# FishTalk_Schematic_1.net
KiCad netlist of a schematic drawn in Altium Designer
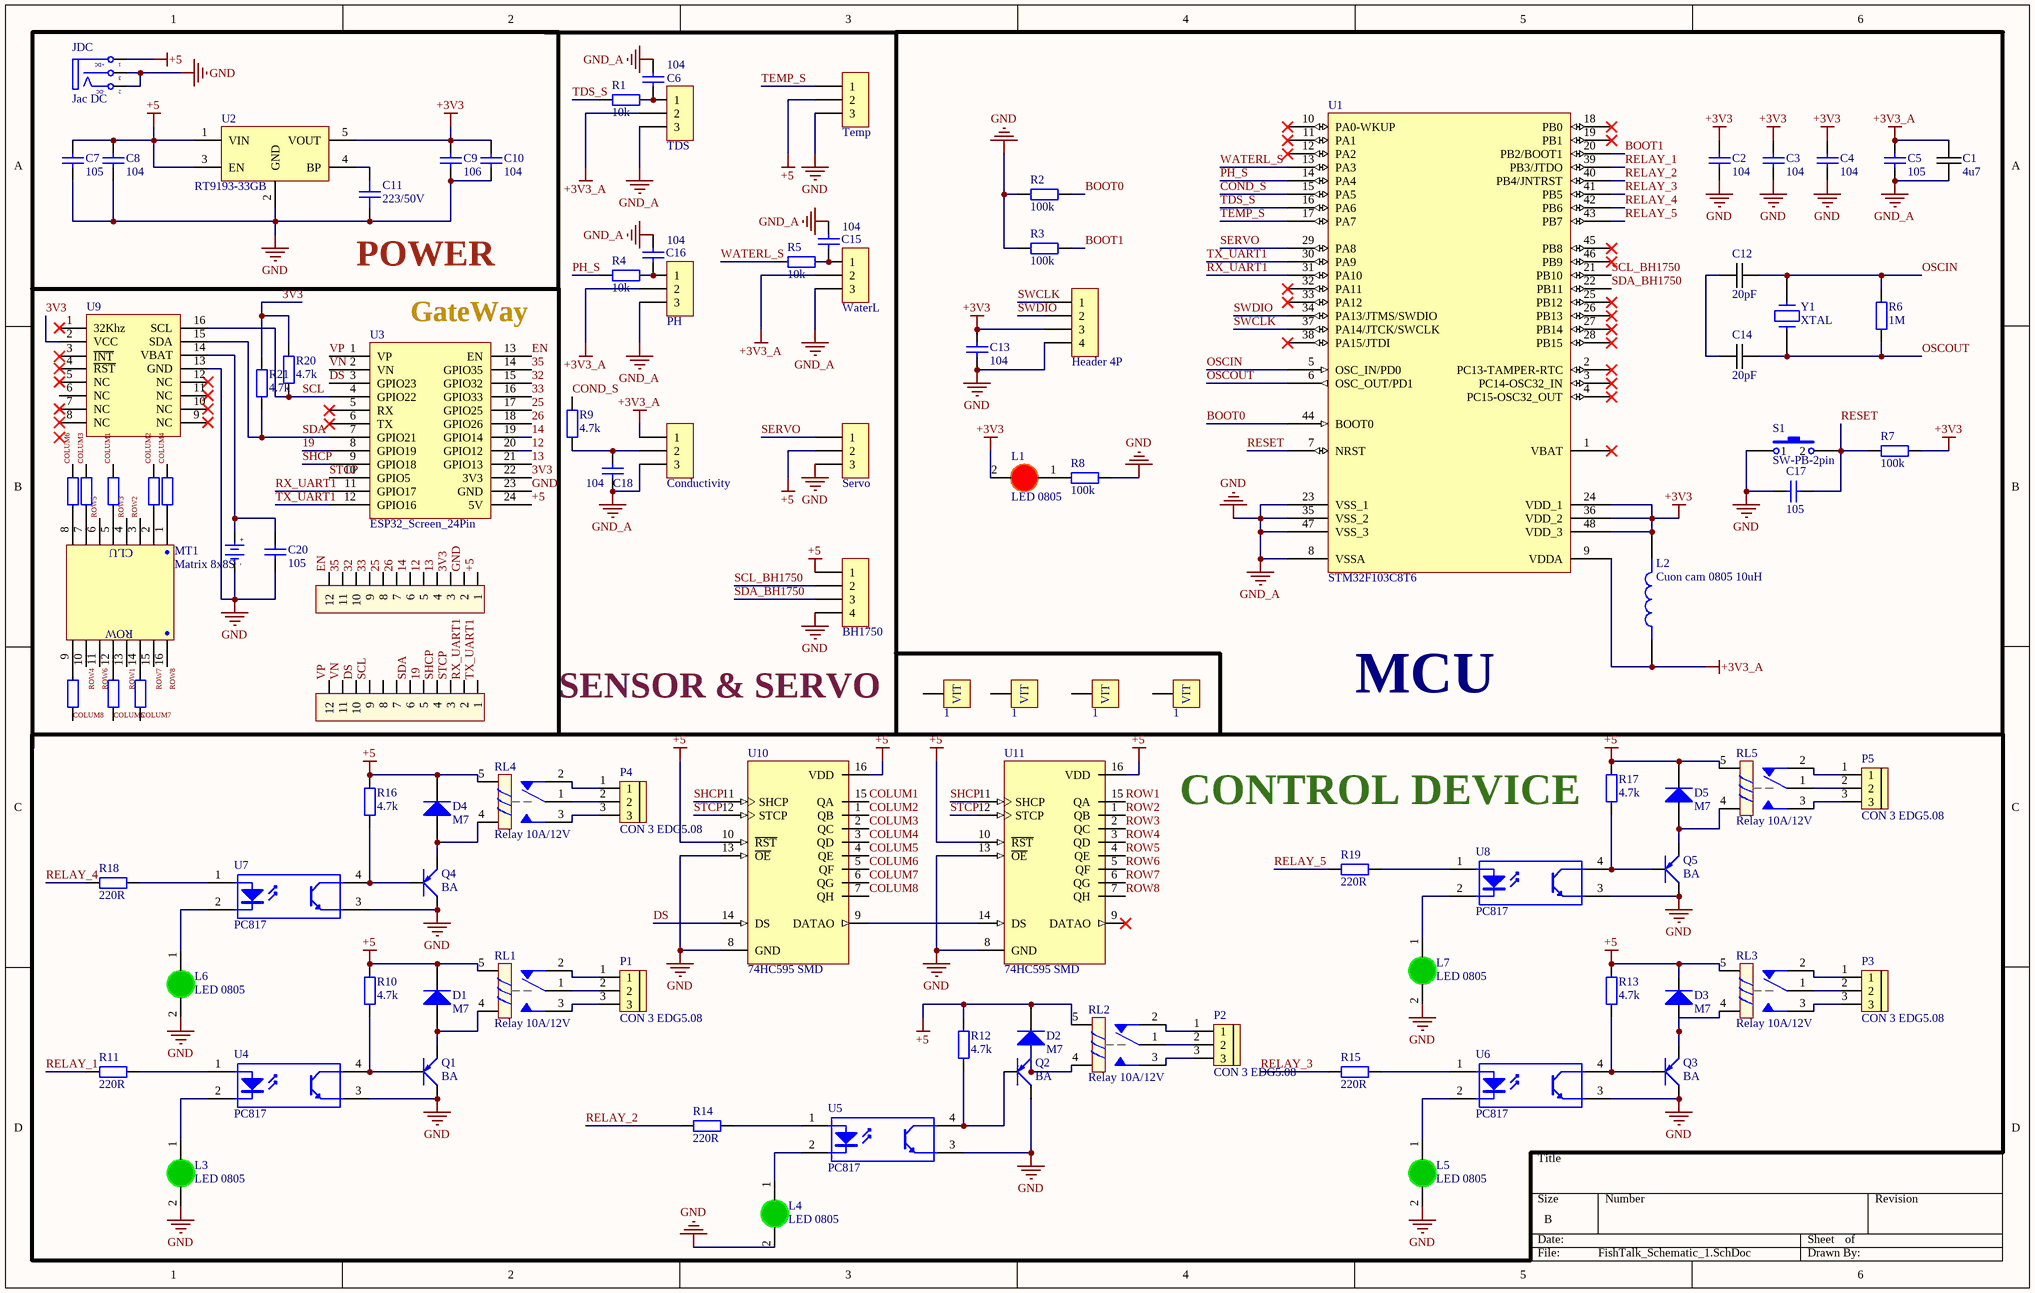
[diagram p0: FishTalk_Schematic_1.SchDoc]

(export (version "E")
  (design (tool "Eeschema 10.0.6"))
  (components
    (comp (ref "BH17")
      (value "BH1750")
      (footprint "XH2.54M-4")
      (description "Cắm")
      (libsource (lib "Header") (part "Header 4P 2.54 Duc Thang"))
    )
    (comp (ref "BT1")
      (value "CR1220 SMD")
      (footprint "DE PIN CR1220")
      (libsource (lib "Component") (part "De pin CR1220 SMD"))
    )
    (comp (ref "C1")
      (value "4u7")
      (footprint "0603C-GENERIC")
      (description "CAPACITOR 0603 CERAMIC")
      (fields
        (field (name "MANUFACTURER PART NUMBER") "C1608X5R1A475K")
        (field (name "MANUFACTURER") "TDK Corporation")
      )
      (libsource (lib "vh_altium_library") (part "0603C-4U7-10V-X5R-TDK"))
    )
    (comp (ref "C2")
      (value "104")
      (footprint "tu 0603")
      (description "Dán")
      (libsource (lib "Tu dien") (part "Tu 0603 104 50V 10%"))
    )
    (comp (ref "C3")
      (value "104")
      (footprint "tu 0603")
      (description "Dán")
      (libsource (lib "Tu dien") (part "Tu 0603 104 50V 10%"))
    )
    (comp (ref "C4")
      (value "104")
      (footprint "tu 0603")
      (description "Dán")
      (libsource (lib "Tu dien") (part "Tu 0603 104 50V 10%"))
    )
    (comp (ref "C5")
      (value "105")
      (footprint "tu 0603")
      (description "Dán")
      (libsource (lib "Tu dien") (part "Tu 0603 105 16V 20%"))
    )
    (comp (ref "C6")
      (value "104")
      (footprint "tu 0603")
      (description "Dán")
      (libsource (lib "Tu dien") (part "Tu 0603 104 50V 10%"))
    )
    (comp (ref "C7")
      (value "105")
      (footprint "tu 0603")
      (description "Dán")
      (libsource (lib "Tu dien") (part "Tu 0603 105 16V 20%"))
    )
    (comp (ref "C8")
      (value "104")
      (footprint "tu 0603")
      (description "Dán")
      (libsource (lib "Tu dien") (part "Tu 0603 104 50V 10%"))
    )
    (comp (ref "C9")
      (value "106")
      (footprint "tu 0603")
      (description "Dán")
      (libsource (lib "Tu dien") (part "Tu 0603 106 16V 20%"))
    )
    (comp (ref "C10")
      (value "104")
      (footprint "tu 0603")
      (description "Dán")
      (libsource (lib "Tu dien") (part "Tu 0603 104 50V 10%"))
    )
    (comp (ref "C11")
      (value "223/50V")
      (footprint "CAPC-0603 (1608)")
      (description "CAP CER 0.022uF 5% 50V X7R 0603")
      (fields (field (name "MPN") "CC0603JRX7R9BB223"))
      (libsource (lib "BYTECH_HW_LIB_2019 (1)") (part "CC0603JRX7R9BB223"))
    )
    (comp (ref "C12")
      (value "20pF")
      (footprint "0603C-GENERIC")
      (description "CAPACITOR 0603 CERAMIC")
      (fields
        (field (name "TOLERANCE") "±5%")
        (field (name "MANUFACTURER") "Murata Electronics North America")
      )
      (libsource (lib "vh_altium_library") (part "0603C-220PF-50V-C0G-MUR"))
    )
    (comp (ref "C13")
      (value "104")
      (footprint "tu 0603")
      (description "Dán")
      (libsource (lib "Tu dien") (part "Tu 0603 104 50V 10%"))
    )
    (comp (ref "C14")
      (value "20pF")
      (footprint "0603C-GENERIC")
      (description "CAPACITOR 0603 CERAMIC")
      (fields
        (field (name "TOLERANCE") "±5%")
        (field (name "MANUFACTURER") "Murata Electronics North America")
      )
      (libsource (lib "vh_altium_library") (part "0603C-220PF-50V-C0G-MUR"))
    )
    (comp (ref "C15")
      (value "104")
      (footprint "tu 0603")
      (description "Dán")
      (libsource (lib "Tu dien") (part "Tu 0603 104 50V 10%"))
    )
    (comp (ref "C16")
      (value "104")
      (footprint "tu 0603")
      (description "Dán")
      (libsource (lib "Tu dien") (part "Tu 0603 104 50V 10%"))
    )
    (comp (ref "C17")
      (value "105")
      (footprint "tu 0805")
      (description "Dán")
      (libsource (lib "Tu dien") (part "Tu 0805 105 50V 10%"))
    )
    (comp (ref "C18")
      (value "104")
      (footprint "tu 0603")
      (description "Dán")
      (libsource (lib "Tu dien") (part "Tu 0603 104 50V 10%"))
    )
    (comp (ref "C20")
      (value "105")
      (footprint "tu 0603")
      (description "Dán")
      (libsource (lib "Tu dien") (part "Tu 0603 105 16V 20%"))
    )
    (comp (ref "COND")
      (value "Conductivity")
      (footprint "XH2.54M-3")
      (description "Cắm")
      (libsource (lib "Header") (part "Header 3P 2.54 Duc Thang"))
    )
    (comp (ref "D1")
      (value "M7")
      (footprint "DIODE SMA")
      (description "Dán")
      (libsource (lib "Diode") (part "Diode M7 ( 4007 )"))
    )
    (comp (ref "D2")
      (value "M7")
      (footprint "DIODE SMA")
      (description "Dán")
      (libsource (lib "Diode") (part "Diode M7 ( 4007 )"))
    )
    (comp (ref "D3")
      (value "M7")
      (footprint "DIODE SMA")
      (description "Dán")
      (libsource (lib "Diode") (part "Diode M7 ( 4007 )"))
    )
    (comp (ref "D4")
      (value "M7")
      (footprint "DIODE SMA")
      (description "Dán")
      (libsource (lib "Diode") (part "Diode M7 ( 4007 )"))
    )
    (comp (ref "D5")
      (value "M7")
      (footprint "DIODE SMA")
      (description "Dán")
      (libsource (lib "Diode") (part "Diode M7 ( 4007 )"))
    )
    (comp (ref "H3")
      (value "Header 4P")
      (footprint "XH2.54M-4")
      (description "Cắm")
      (libsource (lib "Header") (part "Header 4P 2.54 Duc Thang"))
    )
    (comp (ref "H8")
      (value "Header 12P")
      (footprint "XH2.54M-12")
      (description "Cắm")
      (libsource (lib "Header") (part "Header 12P"))
    )
    (comp (ref "H9")
      (value "Header 12P")
      (footprint "XH2.54M-12")
      (description "Cắm")
      (libsource (lib "Header") (part "Header 12P"))
    )
    (comp (ref "JDC")
      (value "Jac DC")
      (footprint "DC-IN")
      (description "Jac DC input")
      (libsource (lib "syhaunguyen") (part "DCIN"))
    )
    (comp (ref "L1")
      (value "LED 0805")
      (footprint "LED-1206-Red")
      (description "Dán")
      (libsource (lib "Led") (part "LED 1206 Do"))
    )
    (comp (ref "L2")
      (value "Cuon cam 0805 10uH")
      (footprint "Inductor 0805")
      (description "1.5ÂµH Unshielded Multilayer Inductor 700mA 220mOhm 0805 (2012 Metric)")
      (fields (field (name "MF") "Laird") (field (name "MP") "CPI0805G1R5R-10"))
      (libsource (lib "Cuon Cam") (part "Cuon cam 0805"))
    )
    (comp (ref "L3")
      (value "LED 0805")
      (footprint "LED-1206-Green")
      (description "Dán")
      (libsource (lib "Led") (part "LED 1206 Xanh La"))
    )
    (comp (ref "L4")
      (value "LED 0805")
      (footprint "LED-1206-Green")
      (description "Dán")
      (libsource (lib "Led") (part "LED 1206 Xanh La"))
    )
    (comp (ref "L5")
      (value "LED 0805")
      (footprint "LED-1206-Green")
      (description "Dán")
      (libsource (lib "Led") (part "LED 1206 Xanh La"))
    )
    (comp (ref "L6")
      (value "LED 0805")
      (footprint "LED-1206-Green")
      (description "Dán")
      (libsource (lib "Led") (part "LED 1206 Xanh La"))
    )
    (comp (ref "L7")
      (value "LED 0805")
      (footprint "LED-1206-Green")
      (description "Dán")
      (libsource (lib "Led") (part "LED 1206 Xanh La"))
    )
    (comp (ref "MT1")
      (value "Matrix 8x8S")
      (footprint "Matrix")
      (description "Matrix 8x8,  Single colour")
      (libsource (lib "Library") (part "LED 8x8S"))
    )
    (comp (ref "P1")
      (value "CON 3 EDG5.08")
      (footprint "Con 3 KF301 5.08")
      (description "Cắm")
      (libsource (lib "Connector") (part "CON 3 EDG5.08"))
    )
    (comp (ref "P2")
      (value "CON 3 EDG5.08")
      (footprint "Con 3 KF301 5.08")
      (description "Cắm")
      (libsource (lib "Connector") (part "CON 3 EDG5.08"))
    )
    (comp (ref "P3")
      (value "CON 3 EDG5.08")
      (footprint "Con 3 KF301 5.08")
      (description "Cắm")
      (libsource (lib "Connector") (part "CON 3 EDG5.08"))
    )
    (comp (ref "P4")
      (value "CON 3 EDG5.08")
      (footprint "Con 3 KF301 5.08")
      (description "Cắm")
      (libsource (lib "Connector") (part "CON 3 EDG5.08"))
    )
    (comp (ref "P5")
      (value "CON 3 EDG5.08")
      (footprint "Con 3 KF301 5.08")
      (description "Cắm")
      (libsource (lib "Connector") (part "CON 3 EDG5.08"))
    )
    (comp (ref "PH")
      (value "PH")
      (footprint "XH2.54M-3")
      (description "Cắm")
      (libsource (lib "Header") (part "Header 3P 2.54 Duc Thang"))
    )
    (comp (ref "Q1")
      (value "BA")
      (footprint "SOT23")
      (description "PNP 600mW, ECB")
      (libsource (lib "TranFet") (part "A1015 BA SMD"))
    )
    (comp (ref "Q2")
      (value "BA")
      (footprint "SOT23")
      (description "PNP 600mW, ECB")
      (libsource (lib "TranFet") (part "A1015 BA SMD"))
    )
    (comp (ref "Q3")
      (value "BA")
      (footprint "SOT23")
      (description "PNP 600mW, ECB")
      (libsource (lib "TranFet") (part "A1015 BA SMD"))
    )
    (comp (ref "Q4")
      (value "BA")
      (footprint "SOT23")
      (description "PNP 600mW, ECB")
      (libsource (lib "TranFet") (part "A1015 BA SMD"))
    )
    (comp (ref "Q5")
      (value "BA")
      (footprint "SOT23")
      (description "PNP 600mW, ECB")
      (libsource (lib "TranFet") (part "A1015 BA SMD"))
    )
    (comp (ref "R1")
      (value "10k")
      (footprint "tro smd 0603")
      (description "Dán")
      (libsource (lib "Dien Tro") (part "Tro 0603 1% 10k"))
    )
    (comp (ref "R2")
      (value "100k")
      (footprint "tro smd 0603")
      (description "Dán")
      (libsource (lib "Dien Tro") (part "Tro 0603 5% 100k"))
    )
    (comp (ref "R3")
      (value "100k")
      (footprint "tro smd 0603")
      (description "Dán")
      (libsource (lib "Dien Tro") (part "Tro 0603 5% 100k"))
    )
    (comp (ref "R4")
      (value "10k")
      (footprint "tro smd 0603")
      (description "Dán")
      (libsource (lib "Dien Tro") (part "Tro 0603 1% 10k"))
    )
    (comp (ref "R5")
      (value "10k")
      (footprint "tro smd 0603")
      (description "Dán")
      (libsource (lib "Dien Tro") (part "Tro 0603 1% 10k"))
    )
    (comp (ref "R6")
      (value "1M")
      (footprint "tro smd 0603")
      (description "Dán")
      (libsource (lib "Dien Tro") (part "Tro 0603 5% 1M"))
    )
    (comp (ref "R7")
      (value "100k")
      (footprint "tro smd 0603")
      (description "Dán")
      (libsource (lib "Dien Tro") (part "Tro 0603 5% 100k"))
    )
    (comp (ref "R8")
      (value "100k")
      (footprint "tro smd 0603")
      (description "Dán")
      (libsource (lib "Dien Tro") (part "Tro 0603 5% 100k"))
    )
    (comp (ref "R9")
      (value "4.7k")
      (footprint "tro smd 0603")
      (description "Dán")
      (libsource (lib "Dien Tro") (part "Tro 0603 1% 10k"))
    )
    (comp (ref "R10")
      (value "4.7k")
      (footprint "tro smd 0603")
      (description "Dán")
      (libsource (lib "Dien Tro") (part "Tro 0603 1% 10k"))
    )
    (comp (ref "R11")
      (value "220R")
      (footprint "tro smd 0603")
      (description "Dán")
      (libsource (lib "Dien Tro") (part "Tro 0603 5% 220R"))
    )
    (comp (ref "R12")
      (value "4.7k")
      (footprint "tro smd 0603")
      (description "Dán")
      (libsource (lib "Dien Tro") (part "Tro 0603 1% 10k"))
    )
    (comp (ref "R13")
      (value "4.7k")
      (footprint "tro smd 0603")
      (description "Dán")
      (libsource (lib "Dien Tro") (part "Tro 0603 1% 10k"))
    )
    (comp (ref "R14")
      (value "220R")
      (footprint "tro smd 0603")
      (description "Dán")
      (libsource (lib "Dien Tro") (part "Tro 0603 5% 220R"))
    )
    (comp (ref "R15")
      (value "220R")
      (footprint "tro smd 0603")
      (description "Dán")
      (libsource (lib "Dien Tro") (part "Tro 0603 5% 220R"))
    )
    (comp (ref "R16")
      (value "4.7k")
      (footprint "tro smd 0603")
      (description "Dán")
      (libsource (lib "Dien Tro") (part "Tro 0603 1% 10k"))
    )
    (comp (ref "R17")
      (value "4.7k")
      (footprint "tro smd 0603")
      (description "Dán")
      (libsource (lib "Dien Tro") (part "Tro 0603 1% 10k"))
    )
    (comp (ref "R18")
      (value "220R")
      (footprint "tro smd 0603")
      (description "Dán")
      (libsource (lib "Dien Tro") (part "Tro 0603 5% 220R"))
    )
    (comp (ref "R19")
      (value "220R")
      (footprint "tro smd 0603")
      (description "Dán")
      (libsource (lib "Dien Tro") (part "Tro 0603 5% 220R"))
    )
    (comp (ref "R20")
      (value "4.7k")
      (footprint "tro smd 0603")
      (description "Dán")
      (libsource (lib "Dien Tro") (part "Tro 0603 1% 10k"))
    )
    (comp (ref "R21")
      (value "4.7k")
      (footprint "tro smd 0603")
      (description "Dán")
      (libsource (lib "Dien Tro") (part "Tro 0603 1% 10k"))
    )
    (comp (ref "R22")
      (value "560R")
      (footprint "tro smd 0603")
      (description "Dán")
      (libsource (lib "Dien Tro") (part "Tro 0603 5% 100k"))
    )
    (comp (ref "R23")
      (value "560R")
      (footprint "tro smd 0603")
      (description "Dán")
      (libsource (lib "Dien Tro") (part "Tro 0603 5% 100k"))
    )
    (comp (ref "R24")
      (value "560R")
      (footprint "tro smd 0603")
      (description "Dán")
      (libsource (lib "Dien Tro") (part "Tro 0603 5% 100k"))
    )
    (comp (ref "R25")
      (value "560R")
      (footprint "tro smd 0603")
      (description "Dán")
      (libsource (lib "Dien Tro") (part "Tro 0603 5% 100k"))
    )
    (comp (ref "R26")
      (value "560R")
      (footprint "tro smd 0603")
      (description "Dán")
      (libsource (lib "Dien Tro") (part "Tro 0603 5% 100k"))
    )
    (comp (ref "R27")
      (value "560R")
      (footprint "tro smd 0603")
      (description "Dán")
      (libsource (lib "Dien Tro") (part "Tro 0603 5% 100k"))
    )
    (comp (ref "R28")
      (value "560R")
      (footprint "tro smd 0603")
      (description "Dán")
      (libsource (lib "Dien Tro") (part "Tro 0603 5% 100k"))
    )
    (comp (ref "R29")
      (value "560R")
      (footprint "tro smd 0603")
      (description "Dán")
      (libsource (lib "Dien Tro") (part "Tro 0603 5% 100k"))
    )
    (comp (ref "RL1")
      (value "Relay 10A/12V")
      (footprint "RL_SPDT_10A")
      (description "Relay SPDT,10A - 12VDC 5 Pin")
      (libsource (lib "syhaunguyen") (part "Relay 1"))
    )
    (comp (ref "RL2")
      (value "Relay 10A/12V")
      (footprint "RL_SPDT_10A")
      (description "Relay SPDT,10A - 12VDC 5 Pin")
      (libsource (lib "syhaunguyen") (part "Relay 1"))
    )
    (comp (ref "RL3")
      (value "Relay 10A/12V")
      (footprint "RL_SPDT_10A")
      (description "Relay SPDT,10A - 12VDC 5 Pin")
      (libsource (lib "syhaunguyen") (part "Relay 1"))
    )
    (comp (ref "RL4")
      (value "Relay 10A/12V")
      (footprint "RL_SPDT_10A")
      (description "Relay SPDT,10A - 12VDC 5 Pin")
      (libsource (lib "syhaunguyen") (part "Relay 1"))
    )
    (comp (ref "RL5")
      (value "Relay 10A/12V")
      (footprint "RL_SPDT_10A")
      (description "Relay SPDT,10A - 12VDC 5 Pin")
      (libsource (lib "syhaunguyen") (part "Relay 1"))
    )
    (comp (ref "S1")
      (value "SW-PB-2pin")
      (footprint "thuvien_altium:SW_B3U-1000P")
      (description "Switch")
      (fields (field (name "PUBLISHER") "Altium Limited"))
      (libsource (lib "thuvien_altium") (part "SW-PB-2pin"))
    )
    (comp (ref "SERVO")
      (value "Servo")
      (footprint "XH2.54M-3")
      (description "Cắm")
      (libsource (lib "Header") (part "Header 3P 2.54 Duc Thang"))
    )
    (comp (ref "TDS")
      (value "TDS")
      (footprint "XH2.54M-3")
      (description "Cắm")
      (libsource (lib "Header") (part "Header 3P 2.54 Duc Thang"))
    )
    (comp (ref "TEMP")
      (value "Temp")
      (footprint "XH2.54M-3")
      (description "Cắm")
      (libsource (lib "Header") (part "Header 3P 2.54 Duc Thang"))
    )
    (comp (ref "U1")
      (value "STM32F103C8T6")
      (footprint "MinhTien_PcbLib:LQFP48_L")
      (description "STM32 ARM-based 32-bit MCU with 64 Kbytes Flash, 48-pin LQFP, Industrial Temperature")
      (fields (field (name "PUBLISHER") "Altium Limited"))
      (libsource (lib "MinhTien_SCHLib") (part "STM32F103C8T6"))
    )
    (comp (ref "U2")
      (value "RT9193-33GB")
      (footprint "MinhTien_PcbLib:SOT23-5AL")
      (description "1A Regulator")
      (libsource (lib "MinhTien_SCHLib") (part "RT9193"))
    )
    (comp (ref "U3")
      (value "ESP32_Screen_24Pin")
      (footprint "ESP32_Module_Screen_24Pin_N3D")
      (libsource (lib "Schlib1_fist_tank") (part "ESP32_Screen_24Pin"))
    )
    (comp (ref "U4")
      (value "PC817")
      (footprint "MinhTien_PCBLib:PhotoCoupler_SMD")
      (description "4-Pin Phototransistor Optocoupler")
      (fields (field (name "PUBLISHER") "Altium Limited"))
      (libsource (lib "MinhTien_SCHLib") (part "PC817"))
    )
    (comp (ref "U5")
      (value "PC817")
      (footprint "MinhTien_PCBLib:PhotoCoupler_SMD")
      (description "4-Pin Phototransistor Optocoupler")
      (fields (field (name "PUBLISHER") "Altium Limited"))
      (libsource (lib "MinhTien_SCHLib") (part "PC817"))
    )
    (comp (ref "U6")
      (value "PC817")
      (footprint "MinhTien_PCBLib:PhotoCoupler_SMD")
      (description "4-Pin Phototransistor Optocoupler")
      (fields (field (name "PUBLISHER") "Altium Limited"))
      (libsource (lib "MinhTien_SCHLib") (part "PC817"))
    )
    (comp (ref "U7")
      (value "PC817")
      (footprint "MinhTien_PCBLib:PhotoCoupler_SMD")
      (description "4-Pin Phototransistor Optocoupler")
      (fields (field (name "PUBLISHER") "Altium Limited"))
      (libsource (lib "MinhTien_SCHLib") (part "PC817"))
    )
    (comp (ref "U8")
      (value "PC817")
      (footprint "MinhTien_PCBLib:PhotoCoupler_SMD")
      (description "4-Pin Phototransistor Optocoupler")
      (fields (field (name "PUBLISHER") "Altium Limited"))
      (libsource (lib "MinhTien_SCHLib") (part "PC817"))
    )
    (comp (ref "U9")
      (value "DS3231 SMD")
      (footprint "SOIC 16")
      (description "SOIC")
      (libsource (lib "IC") (part "DS3231 SMD"))
    )
    (comp (ref "U10")
      (value "74HC595 SMD")
      (footprint "SOP 16")
      (description "Dán")
      (libsource (lib "IC") (part "74HC595 SMD"))
    )
    (comp (ref "U11")
      (value "74HC595 SMD")
      (footprint "SOP 16")
      (description "Dán")
      (libsource (lib "IC") (part "74HC595 SMD"))
    )
    (comp (ref "VIT1")
      (value "1")
      (footprint "Screw octagon 3.81mm")
      (description "Vit xuyen lo")
      (libsource (lib "Connector") (part "VIT"))
    )
    (comp (ref "VIT2")
      (value "1")
      (footprint "Screw octagon 3.81mm")
      (description "Vit xuyen lo")
      (libsource (lib "Connector") (part "VIT"))
    )
    (comp (ref "VIT3")
      (value "1")
      (footprint "Screw octagon 3.81mm")
      (description "Vit xuyen lo")
      (libsource (lib "Connector") (part "VIT"))
    )
    (comp (ref "VIT4")
      (value "1")
      (footprint "Screw octagon 3.81mm")
      (description "Vit xuyen lo")
      (libsource (lib "Connector") (part "VIT"))
    )
    (comp (ref "WATER")
      (value "WaterL")
      (footprint "XH2.54M-3")
      (description "Cắm")
      (libsource (lib "Header") (part "Header 3P 2.54 Duc Thang"))
    )
    (comp (ref "Y1")
      (value "XTAL")
      (footprint "XTAL")
      (description "Crystal")
      (libsource (lib "iDr.ALTIUM") (part "XTAL"))
    )
  )
  (nets
    (net (code "1") (name "+3V3") (class "Default")
      (node (ref "C10") (pin "1") (pinfunction "1_1") (pintype "passive"))
      (node (ref "C13") (pin "1") (pinfunction "1_1") (pintype "passive"))
      (node (ref "C2") (pin "1") (pinfunction "1_1") (pintype "passive"))
      (node (ref "C3") (pin "1") (pinfunction "1_1") (pintype "passive"))
      (node (ref "C4") (pin "1") (pinfunction "1_1") (pintype "passive"))
      (node (ref "C9") (pin "1") (pinfunction "1_1") (pintype "passive"))
      (node (ref "H3") (pin "3") (pinfunction "3_3") (pintype "passive"))
      (node (ref "L1") (pin "2") (pinfunction "K_2") (pintype "passive"))
      (node (ref "L2") (pin "2") (pinfunction "2_2") (pintype "passive"))
      (node (ref "R7") (pin "2") (pinfunction "2_2") (pintype "passive"))
      (node (ref "U1") (pin "24") (pinfunction "VDD_1_24") (pintype "power_in"))
      (node (ref "U1") (pin "36") (pinfunction "VDD_2_36") (pintype "power_in"))
      (node (ref "U1") (pin "48") (pinfunction "VDD_3_48") (pintype "power_in"))
      (node (ref "U2") (pin "5") (pinfunction "VOUT_5") (pintype "passive"))
    )
    (net (code "2") (name "+3V3_A") (class "Default")
      (node (ref "C1") (pin "1") (pintype "passive"))
      (node (ref "C5") (pin "1") (pinfunction "1_1") (pintype "passive"))
      (node (ref "COND") (pin "1") (pinfunction "1_1") (pintype "passive"))
      (node (ref "L2") (pin "1") (pinfunction "1_1") (pintype "passive"))
      (node (ref "PH") (pin "2") (pinfunction "2_2") (pintype "passive"))
      (node (ref "TDS") (pin "2") (pinfunction "2_2") (pintype "passive"))
      (node (ref "U1") (pin "9") (pinfunction "VDDA_9") (pintype "power_in"))
      (node (ref "WATER") (pin "2") (pinfunction "2_2") (pintype "passive"))
    )
    (net (code "3") (name "+5") (class "Default")
      (node (ref "BH17") (pin "1") (pinfunction "1_1") (pintype "passive"))
      (node (ref "C7") (pin "1") (pinfunction "1_1") (pintype "passive"))
      (node (ref "C8") (pin "1") (pinfunction "1_1") (pintype "passive"))
      (node (ref "D1") (pin "2") (pinfunction "K_2") (pintype "passive"))
      (node (ref "D2") (pin "2") (pinfunction "K_2") (pintype "passive"))
      (node (ref "D3") (pin "2") (pinfunction "K_2") (pintype "passive"))
      (node (ref "D4") (pin "2") (pinfunction "K_2") (pintype "passive"))
      (node (ref "D5") (pin "2") (pinfunction "K_2") (pintype "passive"))
      (node (ref "H9") (pin "1") (pinfunction "1_1") (pintype "passive"))
      (node (ref "JDC") (pin "1") (pinfunction "T_1") (pintype "passive"))
      (node (ref "R10") (pin "2") (pinfunction "2_2") (pintype "passive"))
      (node (ref "R12") (pin "2") (pinfunction "2_2") (pintype "passive"))
      (node (ref "R13") (pin "2") (pinfunction "2_2") (pintype "passive"))
      (node (ref "R16") (pin "2") (pinfunction "2_2") (pintype "passive"))
      (node (ref "R17") (pin "2") (pinfunction "2_2") (pintype "passive"))
      (node (ref "RL1") (pin "5") (pinfunction "5_5") (pintype "passive"))
      (node (ref "RL2") (pin "5") (pinfunction "5_5") (pintype "passive"))
      (node (ref "RL3") (pin "5") (pinfunction "5_5") (pintype "passive"))
      (node (ref "RL4") (pin "5") (pinfunction "5_5") (pintype "passive"))
      (node (ref "RL5") (pin "5") (pinfunction "5_5") (pintype "passive"))
      (node (ref "SERVO") (pin "2") (pinfunction "2_2") (pintype "passive"))
      (node (ref "TEMP") (pin "2") (pinfunction "2_2") (pintype "passive"))
      (node (ref "U10") (pin "10") (pinfunction "~{RST}_10") (pintype "input"))
      (node (ref "U10") (pin "16") (pinfunction "VDD_16") (pintype "power_in"))
      (node (ref "U11") (pin "10") (pinfunction "~{RST}_10") (pintype "input"))
      (node (ref "U11") (pin "16") (pinfunction "VDD_16") (pintype "power_in"))
      (node (ref "U2") (pin "1") (pinfunction "VIN_1") (pintype "passive"))
      (node (ref "U2") (pin "3") (pinfunction "EN_3") (pintype "passive"))
      (node (ref "U3") (pin "24") (pinfunction "5V_24") (pintype "passive"))
    )
    (net (code "4") (name "/3V3") (class "Default")
      (node (ref "H9") (pin "3") (pinfunction "3_3") (pintype "passive"))
      (node (ref "R20") (pin "2") (pinfunction "2_2") (pintype "passive"))
      (node (ref "R21") (pin "2") (pinfunction "2_2") (pintype "passive"))
      (node (ref "U3") (pin "22") (pinfunction "3V3_22") (pintype "passive"))
      (node (ref "U9") (pin "2") (pinfunction "VCC_2") (pintype "power_in"))
    )
    (net (code "5") (name "/12") (class "Default")
      (node (ref "H9") (pin "5") (pinfunction "5_5") (pintype "passive"))
      (node (ref "U3") (pin "20") (pinfunction "GPIO12_20") (pintype "passive"))
    )
    (net (code "6") (name "/13") (class "Default")
      (node (ref "H9") (pin "4") (pinfunction "4_4") (pintype "passive"))
      (node (ref "U3") (pin "21") (pinfunction "GPIO13_21") (pintype "passive"))
    )
    (net (code "7") (name "/14") (class "Default")
      (node (ref "H9") (pin "6") (pinfunction "6_6") (pintype "passive"))
      (node (ref "U3") (pin "19") (pinfunction "GPIO14_19") (pintype "passive"))
    )
    (net (code "8") (name "/19") (class "Default")
      (node (ref "H8") (pin "5") (pinfunction "5_5") (pintype "passive"))
      (node (ref "U3") (pin "8") (pinfunction "GPIO19_8") (pintype "passive"))
    )
    (net (code "9") (name "/25") (class "Default")
      (node (ref "H9") (pin "8") (pinfunction "8_8") (pintype "passive"))
      (node (ref "U3") (pin "17") (pinfunction "GPIO25_17") (pintype "passive"))
    )
    (net (code "10") (name "/26") (class "Default")
      (node (ref "H9") (pin "7") (pinfunction "7_7") (pintype "passive"))
      (node (ref "U3") (pin "18") (pinfunction "GPIO26_18") (pintype "passive"))
    )
    (net (code "11") (name "/32") (class "Default")
      (node (ref "H9") (pin "10") (pinfunction "10_10") (pintype "passive"))
      (node (ref "U3") (pin "15") (pinfunction "GPIO32_15") (pintype "passive"))
    )
    (net (code "12") (name "/33") (class "Default")
      (node (ref "H9") (pin "9") (pinfunction "9_9") (pintype "passive"))
      (node (ref "U3") (pin "16") (pinfunction "GPIO33_16") (pintype "passive"))
    )
    (net (code "13") (name "/35") (class "Default")
      (node (ref "H9") (pin "11") (pinfunction "11_11") (pintype "passive"))
      (node (ref "U3") (pin "14") (pinfunction "GPIO35_14") (pintype "passive"))
    )
    (net (code "14") (name "/BOOT0") (class "Default")
      (node (ref "R2") (pin "2") (pinfunction "2_2") (pintype "passive"))
      (node (ref "U1") (pin "44") (pinfunction "BOOT0_44") (pintype "input"))
    )
    (net (code "15") (name "/BOOT1") (class "Default")
      (node (ref "R3") (pin "2") (pinfunction "2_2") (pintype "passive"))
      (node (ref "U1") (pin "20") (pinfunction "PB2/BOOT1_20") (pintype "bidirectional"))
    )
    (net (code "16") (name "/COLUM1") (class "Default")
      (node (ref "R24") (pin "2") (pinfunction "2_2") (pintype "passive"))
      (node (ref "U10") (pin "15") (pinfunction "QA_15") (pintype "tri_state"))
    )
    (net (code "17") (name "/COLUM2") (class "Default")
      (node (ref "R25") (pin "2") (pinfunction "2_2") (pintype "passive"))
      (node (ref "U10") (pin "1") (pinfunction "QB_1") (pintype "tri_state"))
    )
    (net (code "18") (name "/COLUM3") (class "Default")
      (node (ref "R23") (pin "2") (pinfunction "2_2") (pintype "passive"))
      (node (ref "U10") (pin "2") (pinfunction "QC_2") (pintype "tri_state"))
    )
    (net (code "19") (name "/COLUM4") (class "Default")
      (node (ref "R26") (pin "2") (pinfunction "2_2") (pintype "passive"))
      (node (ref "U10") (pin "3") (pinfunction "QD_3") (pintype "tri_state"))
    )
    (net (code "20") (name "/COLUM5") (class "Default")
      (node (ref "R28") (pin "1") (pinfunction "1_1") (pintype "passive"))
      (node (ref "U10") (pin "4") (pinfunction "QE_4") (pintype "tri_state"))
    )
    (net (code "21") (name "/COLUM6") (class "Default")
      (node (ref "R22") (pin "2") (pinfunction "2_2") (pintype "passive"))
      (node (ref "U10") (pin "5") (pinfunction "QF_5") (pintype "tri_state"))
    )
    (net (code "22") (name "/COLUM7") (class "Default")
      (node (ref "R29") (pin "1") (pinfunction "1_1") (pintype "passive"))
      (node (ref "U10") (pin "6") (pinfunction "QG_6") (pintype "tri_state"))
    )
    (net (code "23") (name "/COLUM8") (class "Default")
      (node (ref "R27") (pin "1") (pinfunction "1_1") (pintype "passive"))
      (node (ref "U10") (pin "7") (pinfunction "QH_7") (pintype "tri_state"))
    )
    (net (code "24") (name "/COND_S") (class "Default")
      (node (ref "R9") (pin "1") (pinfunction "1_1") (pintype "passive"))
      (node (ref "U1") (pin "15") (pinfunction "PA5_15") (pintype "bidirectional"))
    )
    (net (code "25") (name "/DS") (class "Default")
      (node (ref "H8") (pin "10") (pinfunction "10_10") (pintype "passive"))
      (node (ref "U10") (pin "14") (pinfunction "DS_14") (pintype "input"))
      (node (ref "U3") (pin "3") (pinfunction "GPIO23_3") (pintype "passive"))
    )
    (net (code "26") (name "/EN") (class "Default")
      (node (ref "H9") (pin "12") (pinfunction "12_12") (pintype "passive"))
      (node (ref "U3") (pin "13") (pinfunction "EN_13") (pintype "passive"))
    )
    (net (code "27") (name "/OSCIN") (class "Default")
      (node (ref "C12") (pin "2") (pintype "passive"))
      (node (ref "R6") (pin "2") (pinfunction "2_2") (pintype "passive"))
      (node (ref "U1") (pin "5") (pinfunction "OSC_IN/PD0_5") (pintype "input"))
      (node (ref "Y1") (pin "2") (pinfunction "2_2") (pintype "passive"))
    )
    (net (code "28") (name "/OSCOUT") (class "Default")
      (node (ref "C14") (pin "2") (pintype "passive"))
      (node (ref "R6") (pin "1") (pinfunction "1_1") (pintype "passive"))
      (node (ref "U1") (pin "6") (pinfunction "OSC_OUT/PD1_6") (pintype "output"))
      (node (ref "Y1") (pin "1") (pinfunction "1_1") (pintype "passive"))
    )
    (net (code "29") (name "/PH_S") (class "Default")
      (node (ref "R4") (pin "1") (pinfunction "1_1") (pintype "passive"))
      (node (ref "U1") (pin "14") (pinfunction "PA4_14") (pintype "bidirectional"))
    )
    (net (code "30") (name "/RELAY_1") (class "Default")
      (node (ref "R11") (pin "1") (pinfunction "1_1") (pintype "passive"))
      (node (ref "U1") (pin "39") (pinfunction "PB3/JTDO_39") (pintype "bidirectional"))
    )
    (net (code "31") (name "/RELAY_2") (class "Default")
      (node (ref "R14") (pin "1") (pinfunction "1_1") (pintype "passive"))
      (node (ref "U1") (pin "40") (pinfunction "PB4/JNTRST_40") (pintype "bidirectional"))
    )
    (net (code "32") (name "/RELAY_3") (class "Default")
      (node (ref "R15") (pin "1") (pinfunction "1_1") (pintype "passive"))
      (node (ref "U1") (pin "41") (pinfunction "PB5_41") (pintype "bidirectional"))
    )
    (net (code "33") (name "/RELAY_4") (class "Default")
      (node (ref "R18") (pin "1") (pinfunction "1_1") (pintype "passive"))
      (node (ref "U1") (pin "42") (pinfunction "PB6_42") (pintype "bidirectional"))
    )
    (net (code "34") (name "/RELAY_5") (class "Default")
      (node (ref "R19") (pin "1") (pinfunction "1_1") (pintype "passive"))
      (node (ref "U1") (pin "43") (pinfunction "PB7_43") (pintype "bidirectional"))
    )
    (net (code "35") (name "/RESET") (class "Default")
      (node (ref "C17") (pin "2") (pinfunction "2_2") (pintype "passive"))
      (node (ref "R7") (pin "1") (pinfunction "1_1") (pintype "passive"))
      (node (ref "S1") (pin "2") (pinfunction "2_2") (pintype "passive"))
      (node (ref "U1") (pin "7") (pinfunction "NRST_7") (pintype "bidirectional"))
    )
    (net (code "36") (name "/ROW1") (class "Default")
      (node (ref "MT1") (pin "13") (pinfunction "H4_13") (pintype "passive"))
      (node (ref "U11") (pin "15") (pinfunction "QA_15") (pintype "tri_state"))
    )
    (net (code "37") (name "/ROW2") (class "Default")
      (node (ref "MT1") (pin "3") (pinfunction "C3_3") (pintype "passive"))
      (node (ref "U11") (pin "1") (pinfunction "QB_1") (pintype "tri_state"))
    )
    (net (code "38") (name "/ROW3") (class "Default")
      (node (ref "MT1") (pin "4") (pinfunction "C4_4") (pintype "passive"))
      (node (ref "U11") (pin "2") (pinfunction "QC_2") (pintype "tri_state"))
    )
    (net (code "39") (name "/ROW4") (class "Default")
      (node (ref "MT1") (pin "10") (pinfunction "H7_10") (pintype "passive"))
      (node (ref "U11") (pin "3") (pinfunction "QD_3") (pintype "tri_state"))
    )
    (net (code "40") (name "/ROW5") (class "Default")
      (node (ref "MT1") (pin "6") (pinfunction "C6_6") (pintype "passive"))
      (node (ref "U11") (pin "4") (pinfunction "QE_4") (pintype "tri_state"))
    )
    (net (code "41") (name "/ROW6") (class "Default")
      (node (ref "MT1") (pin "11") (pinfunction "H6_11") (pintype "passive"))
      (node (ref "U11") (pin "5") (pinfunction "QF_5") (pintype "tri_state"))
    )
    (net (code "42") (name "/ROW7") (class "Default")
      (node (ref "MT1") (pin "15") (pinfunction "H2_15") (pintype "passive"))
      (node (ref "U11") (pin "6") (pinfunction "QG_6") (pintype "tri_state"))
    )
    (net (code "43") (name "/ROW8") (class "Default")
      (node (ref "MT1") (pin "16") (pinfunction "H1_16") (pintype "passive"))
      (node (ref "U11") (pin "7") (pinfunction "QH_7") (pintype "tri_state"))
    )
    (net (code "44") (name "/RX_UART1") (class "Default")
      (node (ref "H8") (pin "2") (pinfunction "2_2") (pintype "passive"))
      (node (ref "U1") (pin "31") (pinfunction "PA10_31") (pintype "bidirectional"))
      (node (ref "U3") (pin "11") (pinfunction "GPIO17_11") (pintype "passive"))
    )
    (net (code "45") (name "/SCL") (class "Default")
      (node (ref "H8") (pin "9") (pinfunction "9_9") (pintype "passive"))
      (node (ref "R20") (pin "1") (pinfunction "1_1") (pintype "passive"))
      (node (ref "U3") (pin "4") (pinfunction "GPIO22_4") (pintype "passive"))
      (node (ref "U9") (pin "16") (pinfunction "SCL_16") (pintype "power_in"))
    )
    (net (code "46") (name "/SCL_BH1750") (class "Default")
      (node (ref "BH17") (pin "2") (pinfunction "2_2") (pintype "passive"))
      (node (ref "U1") (pin "21") (pinfunction "PB10_21") (pintype "bidirectional"))
    )
    (net (code "47") (name "/SDA") (class "Default")
      (node (ref "H8") (pin "6") (pinfunction "6_6") (pintype "passive"))
      (node (ref "R21") (pin "1") (pinfunction "1_1") (pintype "passive"))
      (node (ref "U3") (pin "7") (pinfunction "GPIO21_7") (pintype "passive"))
      (node (ref "U9") (pin "15") (pinfunction "SDA_15") (pintype "power_in"))
    )
    (net (code "48") (name "/SDA_BH1750") (class "Default")
      (node (ref "BH17") (pin "3") (pinfunction "3_3") (pintype "passive"))
      (node (ref "U1") (pin "22") (pinfunction "PB11_22") (pintype "bidirectional"))
    )
    (net (code "49") (name "/SERVO") (class "Default")
      (node (ref "SERVO") (pin "1") (pinfunction "1_1") (pintype "passive"))
      (node (ref "U1") (pin "29") (pinfunction "PA8_29") (pintype "bidirectional"))
    )
    (net (code "50") (name "/SHCP") (class "Default")
      (node (ref "H8") (pin "4") (pinfunction "4_4") (pintype "passive"))
      (node (ref "U10") (pin "11") (pinfunction "SHCP_11") (pintype "input"))
      (node (ref "U11") (pin "11") (pinfunction "SHCP_11") (pintype "input"))
      (node (ref "U3") (pin "9") (pinfunction "GPIO18_9") (pintype "passive"))
    )
    (net (code "51") (name "/STCP") (class "Default")
      (node (ref "H8") (pin "3") (pinfunction "3_3") (pintype "passive"))
      (node (ref "U10") (pin "12") (pinfunction "STCP_12") (pintype "input"))
      (node (ref "U11") (pin "12") (pinfunction "STCP_12") (pintype "input"))
      (node (ref "U3") (pin "10") (pinfunction "GPIO5_10") (pintype "passive"))
    )
    (net (code "52") (name "/SWCLK") (class "Default")
      (node (ref "H3") (pin "1") (pinfunction "1_1") (pintype "passive"))
      (node (ref "U1") (pin "37") (pinfunction "PA14/JTCK/SWCLK_37") (pintype "bidirectional"))
    )
    (net (code "53") (name "/SWDIO") (class "Default")
      (node (ref "H3") (pin "2") (pinfunction "2_2") (pintype "passive"))
      (node (ref "U1") (pin "34") (pinfunction "PA13/JTMS/SWDIO_34") (pintype "bidirectional"))
    )
    (net (code "54") (name "/TDS_S") (class "Default")
      (node (ref "R1") (pin "1") (pinfunction "1_1") (pintype "passive"))
      (node (ref "U1") (pin "16") (pinfunction "PA6_16") (pintype "bidirectional"))
    )
    (net (code "55") (name "/TEMP_S") (class "Default")
      (node (ref "TEMP") (pin "1") (pinfunction "1_1") (pintype "passive"))
      (node (ref "U1") (pin "17") (pinfunction "PA7_17") (pintype "bidirectional"))
    )
    (net (code "56") (name "/TX_UART1") (class "Default")
      (node (ref "H8") (pin "1") (pinfunction "1_1") (pintype "passive"))
      (node (ref "U1") (pin "30") (pinfunction "PA9_30") (pintype "bidirectional"))
      (node (ref "U3") (pin "12") (pinfunction "GPIO16_12") (pintype "passive"))
    )
    (net (code "57") (name "/VN") (class "Default")
      (node (ref "H8") (pin "11") (pinfunction "11_11") (pintype "passive"))
      (node (ref "U3") (pin "2") (pinfunction "VN_2") (pintype "passive"))
    )
    (net (code "58") (name "/VP") (class "Default")
      (node (ref "H8") (pin "12") (pinfunction "12_12") (pintype "passive"))
      (node (ref "U3") (pin "1") (pinfunction "VP_1") (pintype "passive"))
    )
    (net (code "59") (name "/WATERL_S") (class "Default")
      (node (ref "R5") (pin "1") (pinfunction "1_1") (pintype "passive"))
      (node (ref "U1") (pin "13") (pinfunction "PA3_13") (pintype "bidirectional"))
    )
    (net (code "60") (name "GND") (class "Default")
      (node (ref "BH17") (pin "4") (pinfunction "4_4") (pintype "passive"))
      (node (ref "BT1") (pin "2") (pinfunction "GND_2") (pintype "passive"))
      (node (ref "C1") (pin "2") (pintype "passive"))
      (node (ref "C10") (pin "2") (pinfunction "2_2") (pintype "passive"))
      (node (ref "C11") (pin "1") (pinfunction "1_1") (pintype "passive"))
      (node (ref "C13") (pin "2") (pinfunction "2_2") (pintype "passive"))
      (node (ref "C15") (pin "1") (pinfunction "1_1") (pintype "passive"))
      (node (ref "C16") (pin "1") (pinfunction "1_1") (pintype "passive"))
      (node (ref "C17") (pin "1") (pinfunction "1_1") (pintype "passive"))
      (node (ref "C18") (pin "2") (pinfunction "2_2") (pintype "passive"))
      (node (ref "C2") (pin "2") (pinfunction "2_2") (pintype "passive"))
      (node (ref "C20") (pin "2") (pinfunction "2_2") (pintype "passive"))
      (node (ref "C3") (pin "2") (pinfunction "2_2") (pintype "passive"))
      (node (ref "C4") (pin "2") (pinfunction "2_2") (pintype "passive"))
      (node (ref "C5") (pin "2") (pinfunction "2_2") (pintype "passive"))
      (node (ref "C6") (pin "1") (pinfunction "1_1") (pintype "passive"))
      (node (ref "C7") (pin "2") (pinfunction "2_2") (pintype "passive"))
      (node (ref "C8") (pin "2") (pinfunction "2_2") (pintype "passive"))
      (node (ref "C9") (pin "2") (pinfunction "2_2") (pintype "passive"))
      (node (ref "COND") (pin "3") (pinfunction "3_3") (pintype "passive"))
      (node (ref "H3") (pin "4") (pinfunction "4_4") (pintype "passive"))
      (node (ref "H9") (pin "2") (pinfunction "2_2") (pintype "passive"))
      (node (ref "JDC") (pin "2") (pinfunction "TN_2") (pintype "passive"))
      (node (ref "JDC") (pin "3") (pinfunction "S_3") (pintype "power_in"))
      (node (ref "L3") (pin "2") (pinfunction "K_2") (pintype "passive"))
      (node (ref "L4") (pin "2") (pinfunction "K_2") (pintype "passive"))
      (node (ref "L5") (pin "2") (pinfunction "K_2") (pintype "passive"))
      (node (ref "L6") (pin "2") (pinfunction "K_2") (pintype "passive"))
      (node (ref "L7") (pin "2") (pinfunction "K_2") (pintype "passive"))
      (node (ref "PH") (pin "3") (pinfunction "3_3") (pintype "passive"))
      (node (ref "Q1") (pin "3") (pinfunction "C_3") (pintype "passive"))
      (node (ref "Q2") (pin "3") (pinfunction "C_3") (pintype "passive"))
      (node (ref "Q3") (pin "3") (pinfunction "C_3") (pintype "passive"))
      (node (ref "Q4") (pin "3") (pinfunction "C_3") (pintype "passive"))
      (node (ref "Q5") (pin "3") (pinfunction "C_3") (pintype "passive"))
      (node (ref "R2") (pin "1") (pinfunction "1_1") (pintype "passive"))
      (node (ref "R3") (pin "1") (pinfunction "1_1") (pintype "passive"))
      (node (ref "R8") (pin "2") (pinfunction "2_2") (pintype "passive"))
      (node (ref "S1") (pin "1") (pinfunction "1_1") (pintype "passive"))
      (node (ref "SERVO") (pin "3") (pinfunction "3_3") (pintype "passive"))
      (node (ref "TDS") (pin "3") (pinfunction "3_3") (pintype "passive"))
      (node (ref "TEMP") (pin "3") (pinfunction "3_3") (pintype "passive"))
      (node (ref "U1") (pin "23") (pinfunction "VSS_1_23") (pintype "power_in"))
      (node (ref "U1") (pin "35") (pinfunction "VSS_2_35") (pintype "power_in"))
      (node (ref "U1") (pin "47") (pinfunction "VSS_3_47") (pintype "power_in"))
      (node (ref "U1") (pin "8") (pinfunction "VSSA_8") (pintype "power_in"))
      (node (ref "U10") (pin "13") (pinfunction "~{OE}_13") (pintype "input"))
      (node (ref "U10") (pin "8") (pinfunction "GND_8") (pintype "power_in"))
      (node (ref "U11") (pin "13") (pinfunction "~{OE}_13") (pintype "input"))
      (node (ref "U11") (pin "8") (pinfunction "GND_8") (pintype "power_in"))
      (node (ref "U2") (pin "2") (pinfunction "GND_2") (pintype "passive"))
      (node (ref "U3") (pin "23") (pinfunction "GND_23") (pintype "passive"))
      (node (ref "U4") (pin "3") (pinfunction "E_3") (pintype "passive"))
      (node (ref "U5") (pin "3") (pinfunction "E_3") (pintype "passive"))
      (node (ref "U6") (pin "3") (pinfunction "E_3") (pintype "passive"))
      (node (ref "U7") (pin "3") (pinfunction "E_3") (pintype "passive"))
      (node (ref "U8") (pin "3") (pinfunction "E_3") (pintype "passive"))
      (node (ref "U9") (pin "13") (pinfunction "GND_13") (pintype "power_in"))
      (node (ref "WATER") (pin "3") (pinfunction "3_3") (pintype "passive"))
    )
    (net (code "61") (name "Net-(BT1-+3V)") (class "Default")
      (node (ref "BT1") (pin "1") (pinfunction "+3V_1") (pintype "passive"))
      (node (ref "C20") (pin "1") (pinfunction "1_1") (pintype "passive"))
      (node (ref "U9") (pin "14") (pinfunction "VBAT_14") (pintype "power_in"))
    )
    (net (code "62") (name "Net-(C6-Pad2)") (class "Default")
      (node (ref "C6") (pin "2") (pinfunction "2_2") (pintype "passive"))
      (node (ref "R1") (pin "2") (pinfunction "2_2") (pintype "passive"))
      (node (ref "TDS") (pin "1") (pinfunction "1_1") (pintype "passive"))
    )
    (net (code "63") (name "Net-(C12-Pad1)") (class "Default")
      (node (ref "C12") (pin "1") (pintype "passive"))
      (node (ref "C14") (pin "1") (pintype "passive"))
    )
    (net (code "64") (name "Net-(C15-Pad2)") (class "Default")
      (node (ref "C15") (pin "2") (pinfunction "2_2") (pintype "passive"))
      (node (ref "R5") (pin "2") (pinfunction "2_2") (pintype "passive"))
      (node (ref "WATER") (pin "1") (pinfunction "1_1") (pintype "passive"))
    )
    (net (code "65") (name "Net-(C16-Pad2)") (class "Default")
      (node (ref "C16") (pin "2") (pinfunction "2_2") (pintype "passive"))
      (node (ref "PH") (pin "1") (pinfunction "1_1") (pintype "passive"))
      (node (ref "R4") (pin "2") (pinfunction "2_2") (pintype "passive"))
    )
    (net (code "66") (name "Net-(C18-Pad1)") (class "Default")
      (node (ref "C18") (pin "1") (pinfunction "1_1") (pintype "passive"))
      (node (ref "COND") (pin "2") (pinfunction "2_2") (pintype "passive"))
      (node (ref "R9") (pin "2") (pinfunction "2_2") (pintype "passive"))
    )
    (net (code "67") (name "Net-(D1-A)") (class "Default")
      (node (ref "D1") (pin "1") (pinfunction "A_1") (pintype "passive"))
      (node (ref "Q1") (pin "2") (pinfunction "E_2") (pintype "passive"))
      (node (ref "RL1") (pin "4") (pinfunction "4_4") (pintype "passive"))
    )
    (net (code "68") (name "Net-(D2-A)") (class "Default")
      (node (ref "D2") (pin "1") (pinfunction "A_1") (pintype "passive"))
      (node (ref "Q2") (pin "2") (pinfunction "E_2") (pintype "passive"))
      (node (ref "RL2") (pin "4") (pinfunction "4_4") (pintype "passive"))
    )
    (net (code "69") (name "Net-(D3-A)") (class "Default")
      (node (ref "D3") (pin "1") (pinfunction "A_1") (pintype "passive"))
      (node (ref "Q3") (pin "2") (pinfunction "E_2") (pintype "passive"))
      (node (ref "RL3") (pin "4") (pinfunction "4_4") (pintype "passive"))
    )
    (net (code "70") (name "Net-(D4-A)") (class "Default")
      (node (ref "D4") (pin "1") (pinfunction "A_1") (pintype "passive"))
      (node (ref "Q4") (pin "2") (pinfunction "E_2") (pintype "passive"))
      (node (ref "RL4") (pin "4") (pinfunction "4_4") (pintype "passive"))
    )
    (net (code "71") (name "Net-(D5-A)") (class "Default")
      (node (ref "D5") (pin "1") (pinfunction "A_1") (pintype "passive"))
      (node (ref "Q5") (pin "2") (pinfunction "E_2") (pintype "passive"))
      (node (ref "RL5") (pin "4") (pinfunction "4_4") (pintype "passive"))
    )
    (net (code "72") (name "Net-(L1-A)") (class "Default")
      (node (ref "L1") (pin "1") (pinfunction "A_1") (pintype "passive"))
      (node (ref "R8") (pin "1") (pinfunction "1_1") (pintype "passive"))
    )
    (net (code "73") (name "Net-(L3-A)") (class "Default")
      (node (ref "L3") (pin "1") (pinfunction "A_1") (pintype "passive"))
      (node (ref "U4") (pin "2") (pinfunction "K_2") (pintype "passive"))
    )
    (net (code "74") (name "Net-(L4-A)") (class "Default")
      (node (ref "L4") (pin "1") (pinfunction "A_1") (pintype "passive"))
      (node (ref "U5") (pin "2") (pinfunction "K_2") (pintype "passive"))
    )
    (net (code "75") (name "Net-(L5-A)") (class "Default")
      (node (ref "L5") (pin "1") (pinfunction "A_1") (pintype "passive"))
      (node (ref "U6") (pin "2") (pinfunction "K_2") (pintype "passive"))
    )
    (net (code "76") (name "Net-(L6-A)") (class "Default")
      (node (ref "L6") (pin "1") (pinfunction "A_1") (pintype "passive"))
      (node (ref "U7") (pin "2") (pinfunction "K_2") (pintype "passive"))
    )
    (net (code "77") (name "Net-(L7-A)") (class "Default")
      (node (ref "L7") (pin "1") (pinfunction "A_1") (pintype "passive"))
      (node (ref "U8") (pin "2") (pinfunction "K_2") (pintype "passive"))
    )
    (net (code "78") (name "Net-(MT1-C1)") (class "Default")
      (node (ref "MT1") (pin "1") (pinfunction "C1_1") (pintype "passive"))
      (node (ref "R26") (pin "1") (pinfunction "1_1") (pintype "passive"))
    )
    (net (code "79") (name "Net-(MT1-C2)") (class "Default")
      (node (ref "MT1") (pin "2") (pinfunction "C2_2") (pintype "passive"))
      (node (ref "R25") (pin "1") (pinfunction "1_1") (pintype "passive"))
    )
    (net (code "80") (name "Net-(MT1-C5)") (class "Default")
      (node (ref "MT1") (pin "5") (pinfunction "C5_5") (pintype "passive"))
      (node (ref "R24") (pin "1") (pinfunction "1_1") (pintype "passive"))
    )
    (net (code "81") (name "Net-(MT1-C7)") (class "Default")
      (node (ref "MT1") (pin "7") (pinfunction "C7_7") (pintype "passive"))
      (node (ref "R23") (pin "1") (pinfunction "1_1") (pintype "passive"))
    )
    (net (code "82") (name "Net-(MT1-C8)") (class "Default")
      (node (ref "MT1") (pin "8") (pinfunction "C8_8") (pintype "passive"))
      (node (ref "R22") (pin "1") (pinfunction "1_1") (pintype "passive"))
    )
    (net (code "83") (name "Net-(MT1-H3)") (class "Default")
      (node (ref "MT1") (pin "14") (pinfunction "H3_14") (pintype "passive"))
      (node (ref "R29") (pin "2") (pinfunction "2_2") (pintype "passive"))
    )
    (net (code "84") (name "Net-(MT1-H5)") (class "Default")
      (node (ref "MT1") (pin "12") (pinfunction "H5_12") (pintype "passive"))
      (node (ref "R28") (pin "2") (pinfunction "2_2") (pintype "passive"))
    )
    (net (code "85") (name "Net-(MT1-H8)") (class "Default")
      (node (ref "MT1") (pin "9") (pinfunction "H8_9") (pintype "passive"))
      (node (ref "R27") (pin "2") (pinfunction "2_2") (pintype "passive"))
    )
    (net (code "86") (name "Net-(P1-Pad1)") (class "Default")
      (node (ref "P1") (pin "1") (pinfunction "1_1") (pintype "passive"))
      (node (ref "RL1") (pin "2") (pinfunction "2_2") (pintype "passive"))
    )
    (net (code "87") (name "Net-(P1-Pad2)") (class "Default")
      (node (ref "P1") (pin "2") (pinfunction "2_2") (pintype "passive"))
      (node (ref "RL1") (pin "1") (pinfunction "1_1") (pintype "passive"))
    )
    (net (code "88") (name "Net-(P1-Pad3)") (class "Default")
      (node (ref "P1") (pin "3") (pinfunction "3_3") (pintype "passive"))
      (node (ref "RL1") (pin "3") (pinfunction "3_3") (pintype "passive"))
    )
    (net (code "89") (name "Net-(P2-Pad1)") (class "Default")
      (node (ref "P2") (pin "1") (pinfunction "1_1") (pintype "passive"))
      (node (ref "RL2") (pin "2") (pinfunction "2_2") (pintype "passive"))
    )
    (net (code "90") (name "Net-(P2-Pad2)") (class "Default")
      (node (ref "P2") (pin "2") (pinfunction "2_2") (pintype "passive"))
      (node (ref "RL2") (pin "1") (pinfunction "1_1") (pintype "passive"))
    )
    (net (code "91") (name "Net-(P2-Pad3)") (class "Default")
      (node (ref "P2") (pin "3") (pinfunction "3_3") (pintype "passive"))
      (node (ref "RL2") (pin "3") (pinfunction "3_3") (pintype "passive"))
    )
    (net (code "92") (name "Net-(P3-Pad1)") (class "Default")
      (node (ref "P3") (pin "1") (pinfunction "1_1") (pintype "passive"))
      (node (ref "RL3") (pin "2") (pinfunction "2_2") (pintype "passive"))
    )
    (net (code "93") (name "Net-(P3-Pad2)") (class "Default")
      (node (ref "P3") (pin "2") (pinfunction "2_2") (pintype "passive"))
      (node (ref "RL3") (pin "1") (pinfunction "1_1") (pintype "passive"))
    )
    (net (code "94") (name "Net-(P3-Pad3)") (class "Default")
      (node (ref "P3") (pin "3") (pinfunction "3_3") (pintype "passive"))
      (node (ref "RL3") (pin "3") (pinfunction "3_3") (pintype "passive"))
    )
    (net (code "95") (name "Net-(P4-Pad1)") (class "Default")
      (node (ref "P4") (pin "1") (pinfunction "1_1") (pintype "passive"))
      (node (ref "RL4") (pin "2") (pinfunction "2_2") (pintype "passive"))
    )
    (net (code "96") (name "Net-(P4-Pad2)") (class "Default")
      (node (ref "P4") (pin "2") (pinfunction "2_2") (pintype "passive"))
      (node (ref "RL4") (pin "1") (pinfunction "1_1") (pintype "passive"))
    )
    (net (code "97") (name "Net-(P4-Pad3)") (class "Default")
      (node (ref "P4") (pin "3") (pinfunction "3_3") (pintype "passive"))
      (node (ref "RL4") (pin "3") (pinfunction "3_3") (pintype "passive"))
    )
    (net (code "98") (name "Net-(P5-Pad1)") (class "Default")
      (node (ref "P5") (pin "1") (pinfunction "1_1") (pintype "passive"))
      (node (ref "RL5") (pin "2") (pinfunction "2_2") (pintype "passive"))
    )
    (net (code "99") (name "Net-(P5-Pad2)") (class "Default")
      (node (ref "P5") (pin "2") (pinfunction "2_2") (pintype "passive"))
      (node (ref "RL5") (pin "1") (pinfunction "1_1") (pintype "passive"))
    )
    (net (code "100") (name "Net-(P5-Pad3)") (class "Default")
      (node (ref "P5") (pin "3") (pinfunction "3_3") (pintype "passive"))
      (node (ref "RL5") (pin "3") (pinfunction "3_3") (pintype "passive"))
    )
    (net (code "101") (name "Net-(Q1-B)") (class "Default")
      (node (ref "Q1") (pin "1") (pinfunction "B_1") (pintype "passive"))
      (node (ref "R10") (pin "1") (pinfunction "1_1") (pintype "passive"))
      (node (ref "U4") (pin "4") (pinfunction "C_4") (pintype "passive"))
    )
    (net (code "102") (name "Net-(Q2-B)") (class "Default")
      (node (ref "Q2") (pin "1") (pinfunction "B_1") (pintype "passive"))
      (node (ref "R12") (pin "1") (pinfunction "1_1") (pintype "passive"))
      (node (ref "U5") (pin "4") (pinfunction "C_4") (pintype "passive"))
    )
    (net (code "103") (name "Net-(Q3-B)") (class "Default")
      (node (ref "Q3") (pin "1") (pinfunction "B_1") (pintype "passive"))
      (node (ref "R13") (pin "1") (pinfunction "1_1") (pintype "passive"))
      (node (ref "U6") (pin "4") (pinfunction "C_4") (pintype "passive"))
    )
    (net (code "104") (name "Net-(Q4-B)") (class "Default")
      (node (ref "Q4") (pin "1") (pinfunction "B_1") (pintype "passive"))
      (node (ref "R16") (pin "1") (pinfunction "1_1") (pintype "passive"))
      (node (ref "U7") (pin "4") (pinfunction "C_4") (pintype "passive"))
    )
    (net (code "105") (name "Net-(Q5-B)") (class "Default")
      (node (ref "Q5") (pin "1") (pinfunction "B_1") (pintype "passive"))
      (node (ref "R17") (pin "1") (pinfunction "1_1") (pintype "passive"))
      (node (ref "U8") (pin "4") (pinfunction "C_4") (pintype "passive"))
    )
    (net (code "106") (name "Net-(U2-BP)") (class "Default")
      (node (ref "C11") (pin "2") (pinfunction "2_2") (pintype "passive"))
      (node (ref "U2") (pin "4") (pinfunction "BP_4") (pintype "passive"))
    )
    (net (code "107") (name "Net-(U4-A)") (class "Default")
      (node (ref "R11") (pin "2") (pinfunction "2_2") (pintype "passive"))
      (node (ref "U4") (pin "1") (pinfunction "A_1") (pintype "passive"))
    )
    (net (code "108") (name "Net-(U5-A)") (class "Default")
      (node (ref "R14") (pin "2") (pinfunction "2_2") (pintype "passive"))
      (node (ref "U5") (pin "1") (pinfunction "A_1") (pintype "passive"))
    )
    (net (code "109") (name "Net-(U6-A)") (class "Default")
      (node (ref "R15") (pin "2") (pinfunction "2_2") (pintype "passive"))
      (node (ref "U6") (pin "1") (pinfunction "A_1") (pintype "passive"))
    )
    (net (code "110") (name "Net-(U7-A)") (class "Default")
      (node (ref "R18") (pin "2") (pinfunction "2_2") (pintype "passive"))
      (node (ref "U7") (pin "1") (pinfunction "A_1") (pintype "passive"))
    )
    (net (code "111") (name "Net-(U8-A)") (class "Default")
      (node (ref "R19") (pin "2") (pinfunction "2_2") (pintype "passive"))
      (node (ref "U8") (pin "1") (pinfunction "A_1") (pintype "passive"))
    )
    (net (code "112") (name "Net-(U10-DATAO)") (class "Default")
      (node (ref "U10") (pin "9") (pinfunction "DATAO_9") (pintype "output"))
      (node (ref "U11") (pin "14") (pinfunction "DS_14") (pintype "input"))
    )
    (net (code "113") (name "unconnected-(H8-Pad7)") (class "Default")
      (node (ref "H8") (pin "7") (pinfunction "7_7") (pintype "passive"))
    )
    (net (code "114") (name "unconnected-(H8-Pad8)") (class "Default")
      (node (ref "H8") (pin "8") (pinfunction "8_8") (pintype "passive"))
    )
    (net (code "115") (name "unconnected-(U1-PA0-WKUP-Pad10)") (class "Default")
      (node (ref "U1") (pin "10") (pinfunction "PA0-WKUP_10") (pintype "bidirectional+no_connect"))
    )
    (net (code "116") (name "unconnected-(U1-PA1-Pad11)") (class "Default")
      (node (ref "U1") (pin "11") (pinfunction "PA1_11") (pintype "bidirectional+no_connect"))
    )
    (net (code "117") (name "unconnected-(U1-PA2-Pad12)") (class "Default")
      (node (ref "U1") (pin "12") (pinfunction "PA2_12") (pintype "bidirectional+no_connect"))
    )
    (net (code "118") (name "unconnected-(U1-PA11-Pad32)") (class "Default")
      (node (ref "U1") (pin "32") (pinfunction "PA11_32") (pintype "bidirectional+no_connect"))
    )
    (net (code "119") (name "unconnected-(U1-PA12-Pad33)") (class "Default")
      (node (ref "U1") (pin "33") (pinfunction "PA12_33") (pintype "bidirectional+no_connect"))
    )
    (net (code "120") (name "unconnected-(U1-PA15{slash}JTDI-Pad38)") (class "Default")
      (node (ref "U1") (pin "38") (pinfunction "PA15/JTDI_38") (pintype "bidirectional+no_connect"))
    )
    (net (code "121") (name "unconnected-(U1-PB0-Pad18)") (class "Default")
      (node (ref "U1") (pin "18") (pinfunction "PB0_18") (pintype "bidirectional+no_connect"))
    )
    (net (code "122") (name "unconnected-(U1-PB1-Pad19)") (class "Default")
      (node (ref "U1") (pin "19") (pinfunction "PB1_19") (pintype "bidirectional+no_connect"))
    )
    (net (code "123") (name "unconnected-(U1-PB8-Pad45)") (class "Default")
      (node (ref "U1") (pin "45") (pinfunction "PB8_45") (pintype "bidirectional+no_connect"))
    )
    (net (code "124") (name "unconnected-(U1-PB9-Pad46)") (class "Default")
      (node (ref "U1") (pin "46") (pinfunction "PB9_46") (pintype "bidirectional+no_connect"))
    )
    (net (code "125") (name "unconnected-(U1-PB12-Pad25)") (class "Default")
      (node (ref "U1") (pin "25") (pinfunction "PB12_25") (pintype "bidirectional+no_connect"))
    )
    (net (code "126") (name "unconnected-(U1-PB13-Pad26)") (class "Default")
      (node (ref "U1") (pin "26") (pinfunction "PB13_26") (pintype "bidirectional+no_connect"))
    )
    (net (code "127") (name "unconnected-(U1-PB14-Pad27)") (class "Default")
      (node (ref "U1") (pin "27") (pinfunction "PB14_27") (pintype "bidirectional+no_connect"))
    )
    (net (code "128") (name "unconnected-(U1-PB15-Pad28)") (class "Default")
      (node (ref "U1") (pin "28") (pinfunction "PB15_28") (pintype "bidirectional+no_connect"))
    )
    (net (code "129") (name "unconnected-(U1-PC13-TAMPER-RTC-Pad2)") (class "Default")
      (node (ref "U1") (pin "2") (pinfunction "PC13-TAMPER-RTC_2") (pintype "bidirectional+no_connect"))
    )
    (net (code "130") (name "unconnected-(U1-PC14-OSC32_IN-Pad3)") (class "Default")
      (node (ref "U1") (pin "3") (pinfunction "PC14-OSC32_IN_3") (pintype "bidirectional+no_connect"))
    )
    (net (code "131") (name "unconnected-(U1-PC15-OSC32_OUT-Pad4)") (class "Default")
      (node (ref "U1") (pin "4") (pinfunction "PC15-OSC32_OUT_4") (pintype "bidirectional+no_connect"))
    )
    (net (code "132") (name "unconnected-(U1-VBAT-Pad1)") (class "Default")
      (node (ref "U1") (pin "1") (pinfunction "VBAT_1") (pintype "power_in+no_connect"))
    )
    (net (code "133") (name "unconnected-(U3-RX-Pad5)") (class "Default")
      (node (ref "U3") (pin "5") (pinfunction "RX_5") (pintype "passive+no_connect"))
    )
    (net (code "134") (name "unconnected-(U3-TX-Pad6)") (class "Default")
      (node (ref "U3") (pin "6") (pinfunction "TX_6") (pintype "passive+no_connect"))
    )
    (net (code "135") (name "unconnected-(U9-32Khz-Pad1)") (class "Default")
      (node (ref "U9") (pin "1") (pinfunction "32Khz_1") (pintype "power_in+no_connect"))
    )
    (net (code "136") (name "unconnected-(U9-NC-Pad5)") (class "Default")
      (node (ref "U9") (pin "5") (pinfunction "NC_5") (pintype "power_in+no_connect"))
    )
    (net (code "137") (name "unconnected-(U9-NC-Pad6)") (class "Default")
      (node (ref "U9") (pin "6") (pinfunction "NC_6") (pintype "power_in"))
    )
    (net (code "138") (name "unconnected-(U9-NC-Pad7)") (class "Default")
      (node (ref "U9") (pin "7") (pinfunction "NC_7") (pintype "power_in+no_connect"))
    )
    (net (code "139") (name "unconnected-(U9-NC-Pad8)") (class "Default")
      (node (ref "U9") (pin "8") (pinfunction "NC_8") (pintype "power_in+no_connect"))
    )
    (net (code "140") (name "unconnected-(U9-NC-Pad9)") (class "Default")
      (node (ref "U9") (pin "9") (pinfunction "NC_9") (pintype "power_in+no_connect"))
    )
    (net (code "141") (name "unconnected-(U9-NC-Pad10)") (class "Default")
      (node (ref "U9") (pin "10") (pinfunction "NC_10") (pintype "power_in+no_connect"))
    )
    (net (code "142") (name "unconnected-(U9-NC-Pad11)") (class "Default")
      (node (ref "U9") (pin "11") (pinfunction "NC_11") (pintype "power_in+no_connect"))
    )
    (net (code "143") (name "unconnected-(U9-NC-Pad12)") (class "Default")
      (node (ref "U9") (pin "12") (pinfunction "NC_12") (pintype "power_in+no_connect"))
    )
    (net (code "144") (name "unconnected-(U9-~{INT}-Pad3)") (class "Default")
      (node (ref "U9") (pin "3") (pinfunction "~{INT}_3") (pintype "power_in+no_connect"))
    )
    (net (code "145") (name "unconnected-(U9-~{RST}-Pad4)") (class "Default")
      (node (ref "U9") (pin "4") (pinfunction "~{RST}_4") (pintype "power_in+no_connect"))
    )
    (net (code "146") (name "unconnected-(U11-DATAO-Pad9)") (class "Default")
      (node (ref "U11") (pin "9") (pinfunction "DATAO_9") (pintype "output+no_connect"))
    )
    (net (code "147") (name "unconnected-(VIT1-Pad1)") (class "Default")
      (node (ref "VIT1") (pin "1") (pinfunction "1_1") (pintype "passive"))
    )
    (net (code "148") (name "unconnected-(VIT2-Pad1)") (class "Default")
      (node (ref "VIT2") (pin "1") (pinfunction "1_1") (pintype "passive"))
    )
    (net (code "149") (name "unconnected-(VIT3-Pad1)") (class "Default")
      (node (ref "VIT3") (pin "1") (pinfunction "1_1") (pintype "passive"))
    )
    (net (code "150") (name "unconnected-(VIT4-Pad1)") (class "Default")
      (node (ref "VIT4") (pin "1") (pinfunction "1_1") (pintype "passive"))
    )
  )
)
